# 1-Schematic_Power_Board_PCB.net
KiCad netlist of a schematic drawn in EasyEDA
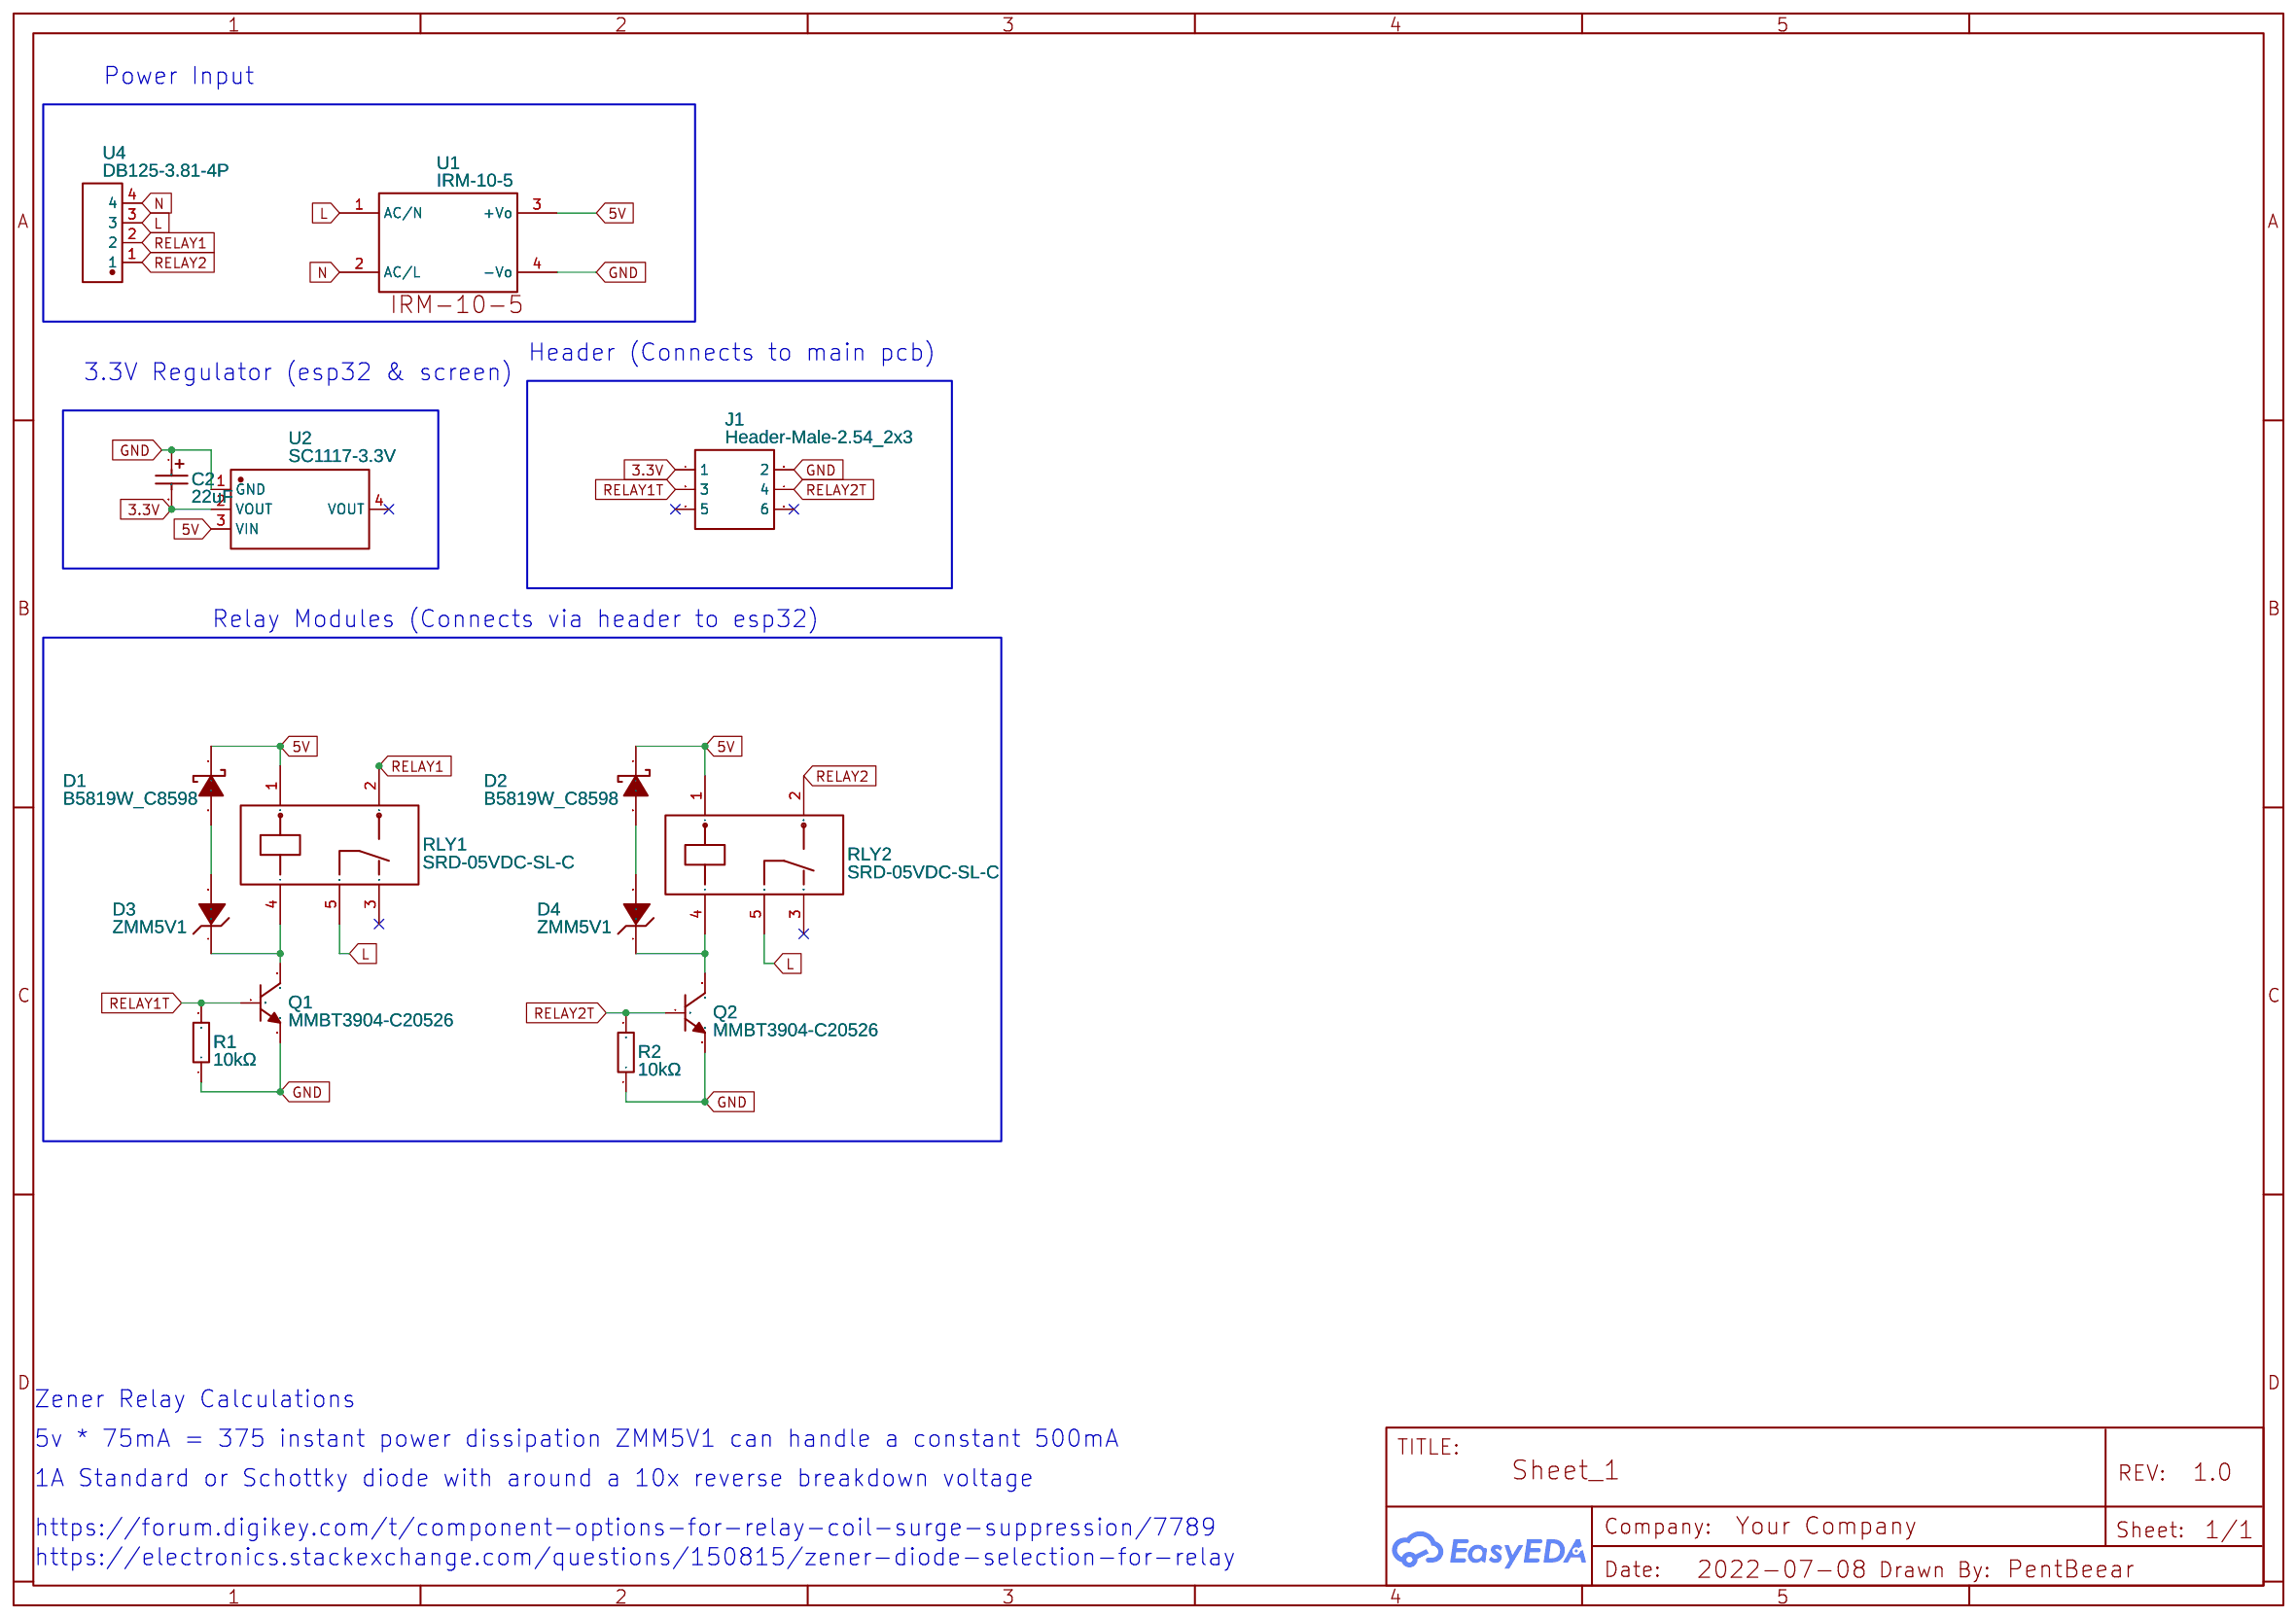
[diagram p0: schematic sheet]

(export (version "E")
  (design (tool "Eeschema 10.0.6"))
  (components
    (comp (ref "C2")
      (value "22uF")
      (fields
        (field (name "BOM_Manufacturer Part") "TAJB226K016RNJ")
        (field (name "BOM_Supplier Part") "C8020")
      )
      (libsource (lib "") (part "TAJB226K016RNJ"))
    )
    (comp (ref "D1")
      (value "B5819W_C8598")
      (fields (field (name "BOM_Manufacturer Part") "B5819W") (field (name "BOM_Supplier Part") "C8598"))
      (libsource (lib "") (part "B5819W_C8598"))
    )
    (comp (ref "D2")
      (value "B5819W_C8598")
      (fields (field (name "BOM_Manufacturer Part") "B5819W") (field (name "BOM_Supplier Part") "C8598"))
      (libsource (lib "") (part "B5819W_C8598"))
    )
    (comp (ref "D3")
      (value "ZMM5V1")
      (fields (field (name "BOM_Supplier Part") "C8061"))
      (libsource (lib "") (part "ZMM5V1"))
    )
    (comp (ref "D4")
      (value "ZMM5V1")
      (fields (field (name "BOM_Supplier Part") "C8061"))
      (libsource (lib "") (part "ZMM5V1"))
    )
    (comp (ref "J1")
      (value "Header-Male-2.54_2x3")
      (fields (field (name "BOM_Supplier Part") "C65114"))
      (libsource (lib "") (part "Header-Male-2.54_2x3"))
    )
    (comp (ref "Q1")
      (value "MMBT3904-C20526")
      (fields (field (name "BOM_Manufacturer Part") "MMBT3904") (field (name "BOM_Supplier Part") "C20526"))
      (libsource (lib "") (part "MMBT3904-C20526"))
    )
    (comp (ref "Q2")
      (value "MMBT3904-C20526")
      (fields (field (name "BOM_Manufacturer Part") "MMBT3904") (field (name "BOM_Supplier Part") "C20526"))
      (libsource (lib "") (part "MMBT3904-C20526"))
    )
    (comp (ref "R1")
      (value "10kΩ")
      (fields
        (field (name "BOM_Manufacturer Part") "RS-05K1002FT")
        (field (name "BOM_Supplier Part") "C115309")
      )
      (libsource (lib "") (part "RS-05K1002FT"))
    )
    (comp (ref "R2")
      (value "10kΩ")
      (fields
        (field (name "BOM_Manufacturer Part") "RS-05K1002FT")
        (field (name "BOM_Supplier Part") "C115309")
      )
      (libsource (lib "") (part "RS-05K1002FT"))
    )
    (comp (ref "RLY1")
      (value "SRD-05VDC-SL-C")
      (fields (field (name "BOM_Supplier Part") "C35449"))
      (libsource (lib "") (part "SRD-05VDC-SL-C"))
    )
    (comp (ref "RLY2")
      (value "SRD-05VDC-SL-C")
      (fields (field (name "BOM_Supplier Part") "C35449"))
      (libsource (lib "") (part "SRD-05VDC-SL-C"))
    )
    (comp (ref "U1")
      (value "IRM-10-5")
      (fields (field (name "BOM_Supplier Part") "NO"))
      (libsource (lib "") (part "IRM-10-5"))
    )
    (comp (ref "U2")
      (value "SC1117-3.3V")
      (fields (field (name "BOM_Supplier Part") "C173386"))
      (libsource (lib "") (part "SC1117-3.3V"))
    )
    (comp (ref "U4")
      (value "DB125-3.81-4P")
      (fields (field (name "BOM_Supplier Part") "C395880"))
      (libsource (lib "") (part "DB125-3.81-4P"))
    )
  )
  (nets
    (net (code "1") (name "3.3V") (class "Default")
      (node (ref "C2") (pin "2") (pinfunction "2_2") (pintype "input"))
      (node (ref "J1") (pin "1") (pinfunction "1_1") (pintype "input"))
      (node (ref "U2") (pin "2") (pinfunction "VOUT_2") (pintype "unspecified"))
    )
    (net (code "2") (name "5V") (class "Default")
      (node (ref "D1") (pin "1") (pinfunction "-_1") (pintype "unspecified"))
      (node (ref "D2") (pin "1") (pinfunction "-_1") (pintype "unspecified"))
      (node (ref "RLY1") (pin "1") (pinfunction "1_1") (pintype "input"))
      (node (ref "RLY2") (pin "1") (pinfunction "1_1") (pintype "input"))
      (node (ref "U1") (pin "3") (pinfunction "+Vo_3") (pintype "unspecified"))
      (node (ref "U2") (pin "3") (pinfunction "VIN_3") (pintype "unspecified"))
    )
    (net (code "3") (name "GND") (class "Default")
      (node (ref "C2") (pin "1") (pinfunction "1_1") (pintype "input"))
      (node (ref "J1") (pin "2") (pinfunction "2_2") (pintype "input"))
      (node (ref "Q1") (pin "2") (pinfunction "E_2") (pintype "unspecified"))
      (node (ref "Q2") (pin "2") (pinfunction "E_2") (pintype "unspecified"))
      (node (ref "R1") (pin "1") (pinfunction "1_1") (pintype "input"))
      (node (ref "R2") (pin "1") (pinfunction "1_1") (pintype "input"))
      (node (ref "U1") (pin "4") (pinfunction "-Vo_4") (pintype "unspecified"))
      (node (ref "U2") (pin "1") (pinfunction "GND_1") (pintype "unspecified"))
    )
    (net (code "4") (name "L") (class "Default")
      (node (ref "RLY1") (pin "5") (pinfunction "5_5") (pintype "input"))
      (node (ref "RLY2") (pin "5") (pinfunction "5_5") (pintype "input"))
      (node (ref "U1") (pin "1") (pinfunction "AC/N_1") (pintype "unspecified"))
      (node (ref "U4") (pin "3") (pinfunction "3_3") (pintype "unspecified"))
    )
    (net (code "5") (name "N") (class "Default")
      (node (ref "U1") (pin "2") (pinfunction "AC/L_2") (pintype "unspecified"))
      (node (ref "U4") (pin "4") (pinfunction "4_4") (pintype "unspecified"))
    )
    (net (code "6") (name "Net-(D1-+)") (class "Default")
      (node (ref "D1") (pin "2") (pinfunction "+_2") (pintype "unspecified"))
      (node (ref "D3") (pin "2") (pinfunction "A_2") (pintype "unspecified"))
    )
    (net (code "7") (name "Net-(D2-+)") (class "Default")
      (node (ref "D2") (pin "2") (pinfunction "+_2") (pintype "unspecified"))
      (node (ref "D4") (pin "2") (pinfunction "A_2") (pintype "unspecified"))
    )
    (net (code "8") (name "Net-(D3-C)") (class "Default")
      (node (ref "D3") (pin "1") (pinfunction "C_1") (pintype "unspecified"))
      (node (ref "Q1") (pin "3") (pinfunction "C_3") (pintype "unspecified"))
      (node (ref "RLY1") (pin "4") (pinfunction "4_4") (pintype "input"))
    )
    (net (code "9") (name "Net-(D4-C)") (class "Default")
      (node (ref "D4") (pin "1") (pinfunction "C_1") (pintype "unspecified"))
      (node (ref "Q2") (pin "3") (pinfunction "C_3") (pintype "unspecified"))
      (node (ref "RLY2") (pin "4") (pinfunction "4_4") (pintype "input"))
    )
    (net (code "10") (name "RELAY1") (class "Default")
      (node (ref "RLY1") (pin "2") (pinfunction "2_2") (pintype "input"))
      (node (ref "U4") (pin "2") (pinfunction "2_2") (pintype "unspecified"))
    )
    (net (code "11") (name "RELAY1T") (class "Default")
      (node (ref "J1") (pin "3") (pinfunction "3_3") (pintype "input"))
      (node (ref "Q1") (pin "1") (pinfunction "B_1") (pintype "unspecified"))
      (node (ref "R1") (pin "2") (pinfunction "2_2") (pintype "input"))
    )
    (net (code "12") (name "RELAY2") (class "Default")
      (node (ref "RLY2") (pin "2") (pinfunction "2_2") (pintype "input"))
      (node (ref "U4") (pin "1") (pinfunction "1_1") (pintype "unspecified"))
    )
    (net (code "13") (name "RELAY2T") (class "Default")
      (node (ref "J1") (pin "4") (pinfunction "4_4") (pintype "input"))
      (node (ref "Q2") (pin "1") (pinfunction "B_1") (pintype "unspecified"))
      (node (ref "R2") (pin "2") (pinfunction "2_2") (pintype "input"))
    )
    (net (code "14") (name "unconnected-(J1-Pad5)") (class "Default")
      (node (ref "J1") (pin "5") (pinfunction "5_5") (pintype "input+no_connect"))
    )
    (net (code "15") (name "unconnected-(J1-Pad6)") (class "Default")
      (node (ref "J1") (pin "6") (pinfunction "6_6") (pintype "input+no_connect"))
    )
    (net (code "16") (name "unconnected-(RLY1-Pad3)") (class "Default")
      (node (ref "RLY1") (pin "3") (pinfunction "3_3") (pintype "input+no_connect"))
    )
    (net (code "17") (name "unconnected-(RLY2-Pad3)") (class "Default")
      (node (ref "RLY2") (pin "3") (pinfunction "3_3") (pintype "input+no_connect"))
    )
    (net (code "18") (name "unconnected-(U2-VOUT-Pad4)") (class "Default")
      (node (ref "U2") (pin "4") (pinfunction "VOUT_4") (pintype "unspecified+no_connect"))
    )
  )
)
